# blink1_v2c.net
KiCad netlist of a schematic drawn in EAGLE
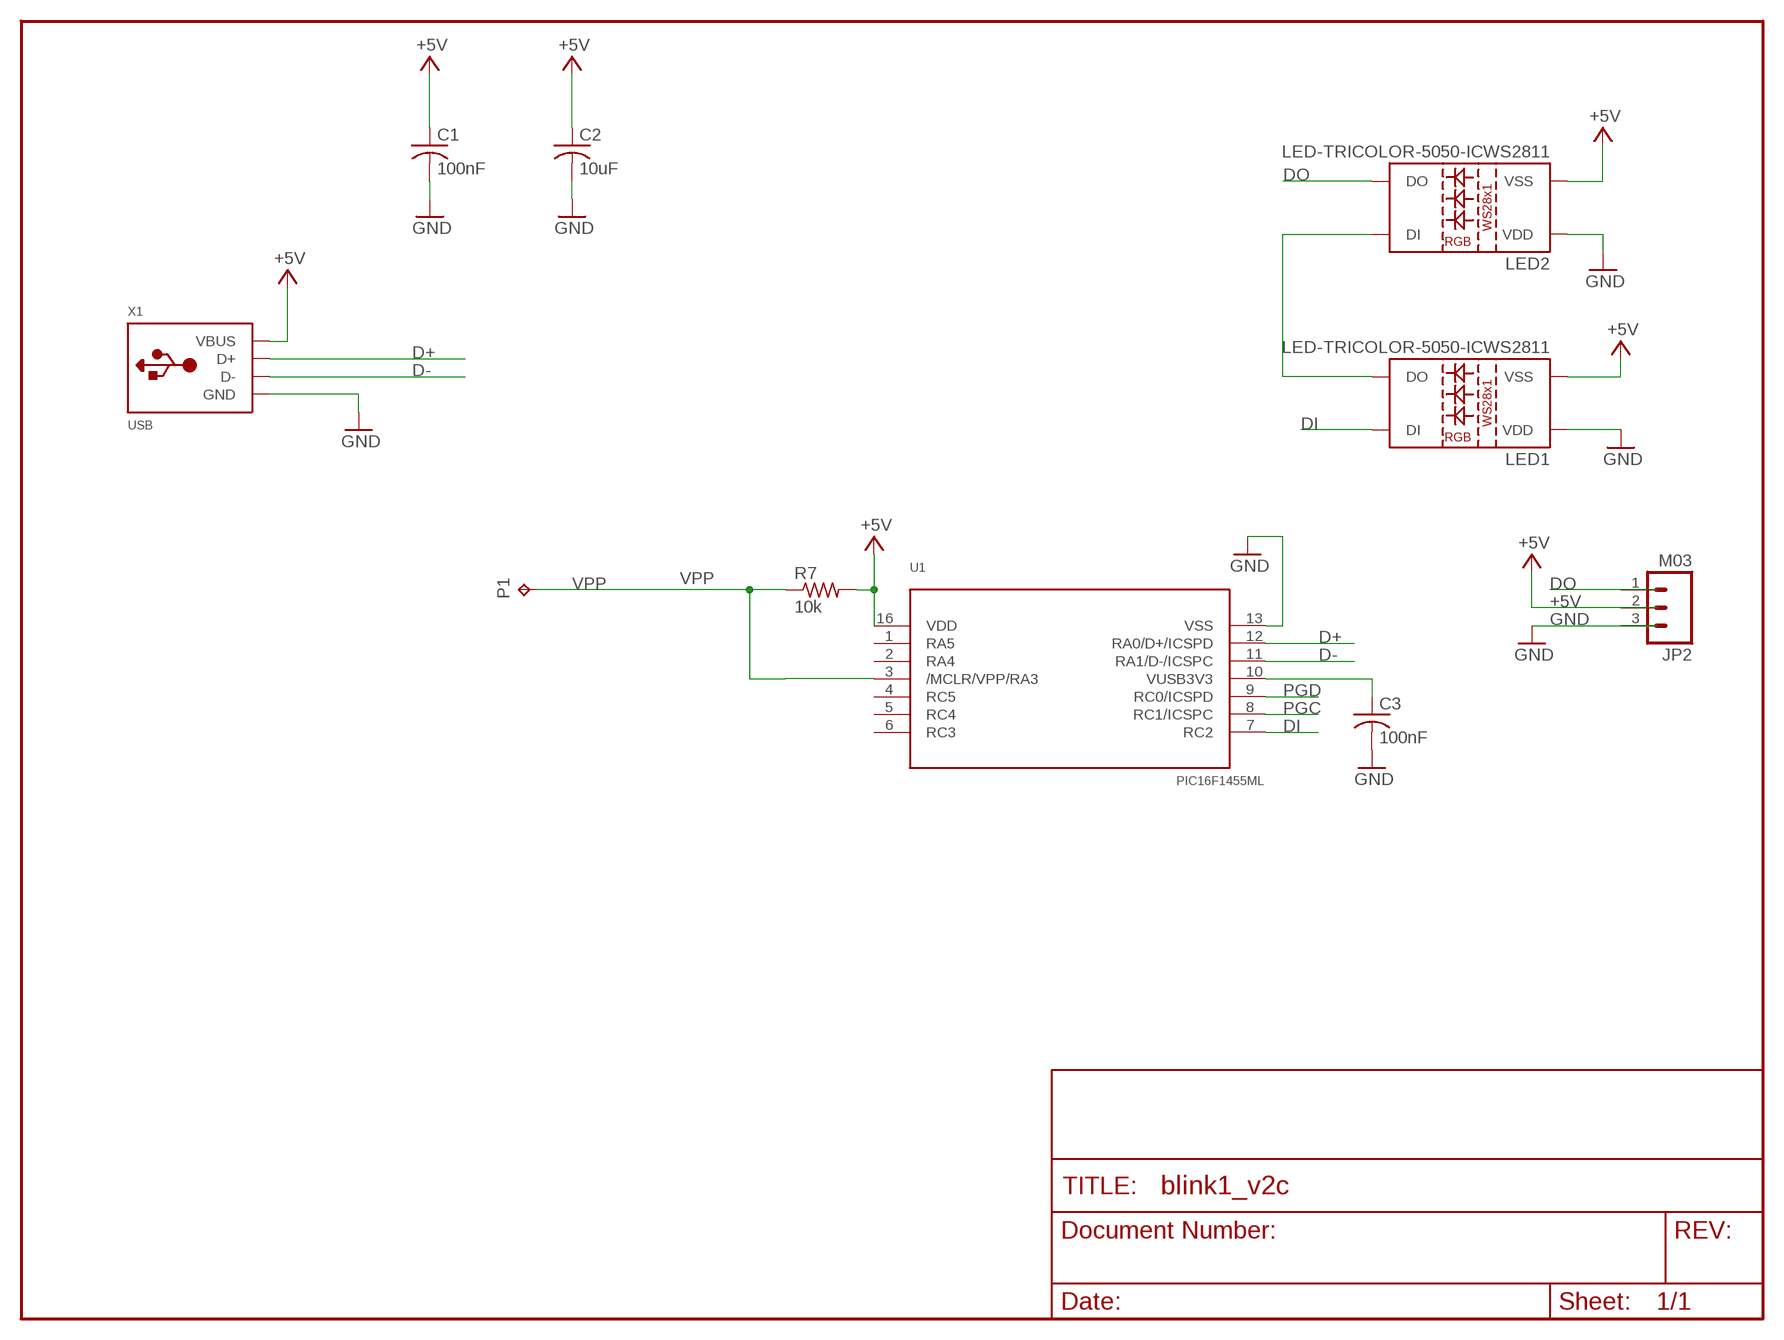
[diagram p0: schematic, sheet 1]

(export (version "E")
  (design (tool "Eeschema 10.0.6"))
  (components
    (comp (ref "C1")
      (value "100nF")
      (footprint "eagle-import:C0603")
      (libsource (lib "eagle-import") (part "C-USC0603"))
    )
    (comp (ref "C2")
      (value "10uF")
      (footprint "eagle-import:C0603")
      (libsource (lib "eagle-import") (part "C-USC0603"))
    )
    (comp (ref "C3")
      (value "100nF")
      (footprint "eagle-import:C0603")
      (libsource (lib "eagle-import") (part "C-USC0603"))
    )
    (comp (ref "JP2")
      (value "M03")
      (footprint "eagle-import:1X03-1.27MM")
      (libsource (lib "eagle-import") (part "M03"))
    )
    (comp (ref "LED1")
      (value "LED-TRICOLOR-5050-ICWS2811")
      (footprint "eagle-import:LED-TRICOLOR-5050-IC")
      (libsource (lib "eagle-import") (part "LED-TRICOLOR-5050-ICWS2811"))
    )
    (comp (ref "LED2")
      (value "LED-TRICOLOR-5050-ICWS2811")
      (footprint "eagle-import:LED-TRICOLOR-5050-IC")
      (libsource (lib "eagle-import") (part "LED-TRICOLOR-5050-ICWS2811"))
    )
    (comp (ref "P1")
      (value "TPTP11SQ")
      (footprint "eagle-import:TP11SQ")
      (libsource (lib "eagle-import") (part "TPTP11SQ"))
    )
    (comp (ref "R7")
      (value "10k")
      (footprint "eagle-import:R0603")
      (libsource (lib "eagle-import") (part "R-US_R0603"))
    )
    (comp (ref "U1")
      (value "PIC16F1455ML")
      (footprint "eagle-import:QFN16_4X4")
      (libsource (lib "eagle-import") (part "PIC16F1455ML"))
    )
    (comp (ref "X1")
      (value "USB")
      (footprint "eagle-import:MOLEX-48037-1000")
      (libsource (lib "eagle-import") (part "USB"))
    )
  )
  (nets
    (net (code "1") (name "+5V") (class "Default")
      (node (ref "C1") (pin "1") (pinfunction "1_1") (pintype "passive"))
      (node (ref "C2") (pin "1") (pinfunction "1_1") (pintype "passive"))
      (node (ref "JP2") (pin "2") (pinfunction "2_2") (pintype "passive"))
      (node (ref "LED1") (pin "6") (pinfunction "VSS_6") (pintype "bidirectional"))
      (node (ref "LED2") (pin "6") (pinfunction "VSS_6") (pintype "bidirectional"))
      (node (ref "R7") (pin "2") (pinfunction "2_2") (pintype "passive"))
      (node (ref "U1") (pin "16") (pinfunction "VDD_16") (pintype "bidirectional"))
      (node (ref "X1") (pin "1") (pinfunction "VBUS_1") (pintype "power_in"))
    )
    (net (code "2") (name "/D+") (class "Default")
      (node (ref "U1") (pin "12") (pinfunction "RA0/D+/ICSPD_12") (pintype "bidirectional"))
      (node (ref "X1") (pin "3") (pinfunction "D+_3") (pintype "bidirectional"))
    )
    (net (code "3") (name "/D-") (class "Default")
      (node (ref "U1") (pin "11") (pinfunction "RA1/D-/ICSPC_11") (pintype "bidirectional"))
      (node (ref "X1") (pin "2") (pinfunction "D-_2") (pintype "bidirectional"))
    )
    (net (code "4") (name "/DI") (class "Default")
      (node (ref "LED1") (pin "2") (pinfunction "DI_2") (pintype "bidirectional"))
      (node (ref "U1") (pin "7") (pinfunction "RC2_7") (pintype "bidirectional"))
    )
    (net (code "5") (name "/DO") (class "Default")
      (node (ref "JP2") (pin "1") (pinfunction "1_1") (pintype "passive"))
      (node (ref "LED2") (pin "1") (pinfunction "DO_1") (pintype "bidirectional"))
    )
    (net (code "6") (name "/PGC") (class "Default")
      (node (ref "U1") (pin "8") (pinfunction "RC1/ICSPC_8") (pintype "bidirectional"))
    )
    (net (code "7") (name "/PGD") (class "Default")
      (node (ref "U1") (pin "9") (pinfunction "RC0/ICSPD_9") (pintype "bidirectional"))
    )
    (net (code "8") (name "/VPP") (class "Default")
      (node (ref "P1") (pin "TP") (pinfunction "TP_TP") (pintype "input"))
      (node (ref "R7") (pin "1") (pinfunction "1_1") (pintype "passive"))
      (node (ref "U1") (pin "3") (pinfunction "/MCLR/VPP/RA3_3") (pintype "bidirectional"))
    )
    (net (code "9") (name "GND") (class "Default")
      (node (ref "C1") (pin "2") (pinfunction "2_2") (pintype "passive"))
      (node (ref "C2") (pin "2") (pinfunction "2_2") (pintype "passive"))
      (node (ref "C3") (pin "2") (pinfunction "2_2") (pintype "passive"))
      (node (ref "JP2") (pin "3") (pinfunction "3_3") (pintype "passive"))
      (node (ref "LED1") (pin "3") (pinfunction "VDD_3") (pintype "bidirectional"))
      (node (ref "LED1") (pin "5") (pinfunction "VDD_5") (pintype "bidirectional"))
      (node (ref "LED2") (pin "3") (pinfunction "VDD_3") (pintype "bidirectional"))
      (node (ref "LED2") (pin "5") (pinfunction "VDD_5") (pintype "bidirectional"))
      (node (ref "U1") (pin "13") (pinfunction "VSS_13") (pintype "bidirectional"))
      (node (ref "X1") (pin "4") (pinfunction "GND_4") (pintype "power_in"))
    )
    (net (code "10") (name "Net-(LED1-DO)") (class "Default")
      (node (ref "LED1") (pin "1") (pinfunction "DO_1") (pintype "bidirectional"))
      (node (ref "LED2") (pin "2") (pinfunction "DI_2") (pintype "bidirectional"))
    )
    (net (code "11") (name "Net-(U1-VUSB3V3)") (class "Default")
      (node (ref "C3") (pin "1") (pinfunction "1_1") (pintype "passive"))
      (node (ref "U1") (pin "10") (pinfunction "VUSB3V3_10") (pintype "bidirectional"))
    )
    (net (code "12") (name "unconnected-(U1-RA4-Pad2)") (class "Default")
      (node (ref "U1") (pin "2") (pinfunction "RA4_2") (pintype "bidirectional"))
    )
    (net (code "13") (name "unconnected-(U1-RA5-Pad1)") (class "Default")
      (node (ref "U1") (pin "1") (pinfunction "RA5_1") (pintype "bidirectional"))
    )
    (net (code "14") (name "unconnected-(U1-RC3-Pad6)") (class "Default")
      (node (ref "U1") (pin "6") (pinfunction "RC3_6") (pintype "bidirectional"))
    )
    (net (code "15") (name "unconnected-(U1-RC4-Pad5)") (class "Default")
      (node (ref "U1") (pin "5") (pinfunction "RC4_5") (pintype "bidirectional"))
    )
    (net (code "16") (name "unconnected-(U1-RC5-Pad4)") (class "Default")
      (node (ref "U1") (pin "4") (pinfunction "RC5_4") (pintype "bidirectional"))
    )
  )
)
